# others.net
KiCad netlist of a schematic drawn in Altium Designer
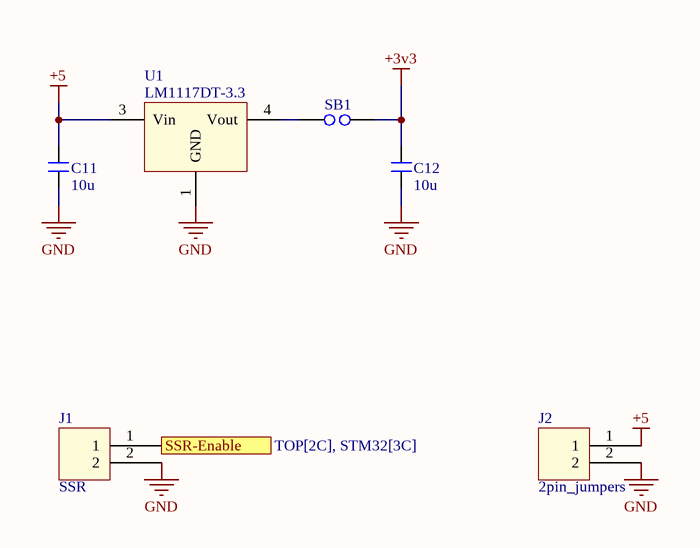
[diagram p0: others.SchDoc]

(export (version "E")
  (design (tool "Eeschema 10.0.6"))
  (components
    (comp (ref "C11") (value "10u") (footprint "0805") (libsource (lib "capacitor") (part "capacitor")))
    (comp (ref "C12") (value "10u") (footprint "0805") (libsource (lib "capacitor") (part "capacitor")))
    (comp (ref "J1") (value "SSR") (footprint "2pin") (libsource (lib "SSR") (part "SSR")))
    (comp (ref "J2")
      (value "2pin_jumpers")
      (footprint "2pinpwd")
      (libsource (lib "2pin_jumpers") (part "2pin_jumpers"))
    )
    (comp (ref "SB1")
      (value "SolderBrige")
      (footprint "SolderBrige")
      (libsource (lib "SolderBrige") (part "SolderBrige"))
    )
    (comp (ref "U1")
      (value "LM1117DT-3.3")
      (footprint "LM1117DT-3.3")
      (libsource (lib "LM1117DT-3.3") (part "LM1117DT-3.3"))
    )
  )
  (nets
    (net (code "1") (name "+3v3") (class "Default")
      (node (ref "C12") (pin "1") (pinfunction "1_1") (pintype "passive"))
      (node (ref "SB1") (pin "1") (pinfunction "1_1") (pintype "passive"))
    )
    (net (code "2") (name "+5") (class "Default")
      (node (ref "C11") (pin "1") (pinfunction "1_1") (pintype "passive"))
      (node (ref "J2") (pin "1") (pinfunction "1_1") (pintype "passive"))
      (node (ref "U1") (pin "3") (pinfunction "Vin_3") (pintype "power_in"))
    )
    (net (code "3") (name "/SSR-Enable") (class "Default")
      (node (ref "J1") (pin "1") (pinfunction "1_1") (pintype "passive"))
    )
    (net (code "4") (name "GND") (class "Default")
      (node (ref "C11") (pin "2") (pintype "passive"))
      (node (ref "C12") (pin "2") (pintype "passive"))
      (node (ref "J1") (pin "2") (pinfunction "2_2") (pintype "passive"))
      (node (ref "J2") (pin "2") (pinfunction "2_2") (pintype "passive"))
      (node (ref "U1") (pin "1") (pinfunction "GND_1") (pintype "power_in"))
    )
    (net (code "5") (name "Net-(U1-Vout)") (class "Default")
      (node (ref "SB1") (pin "2") (pinfunction "2_2") (pintype "passive"))
      (node (ref "U1") (pin "4") (pinfunction "Vout_4") (pintype "power_in"))
    )
  )
)
